# battiny_power_breakout.net
KiCad netlist of a schematic drawn in EAGLE
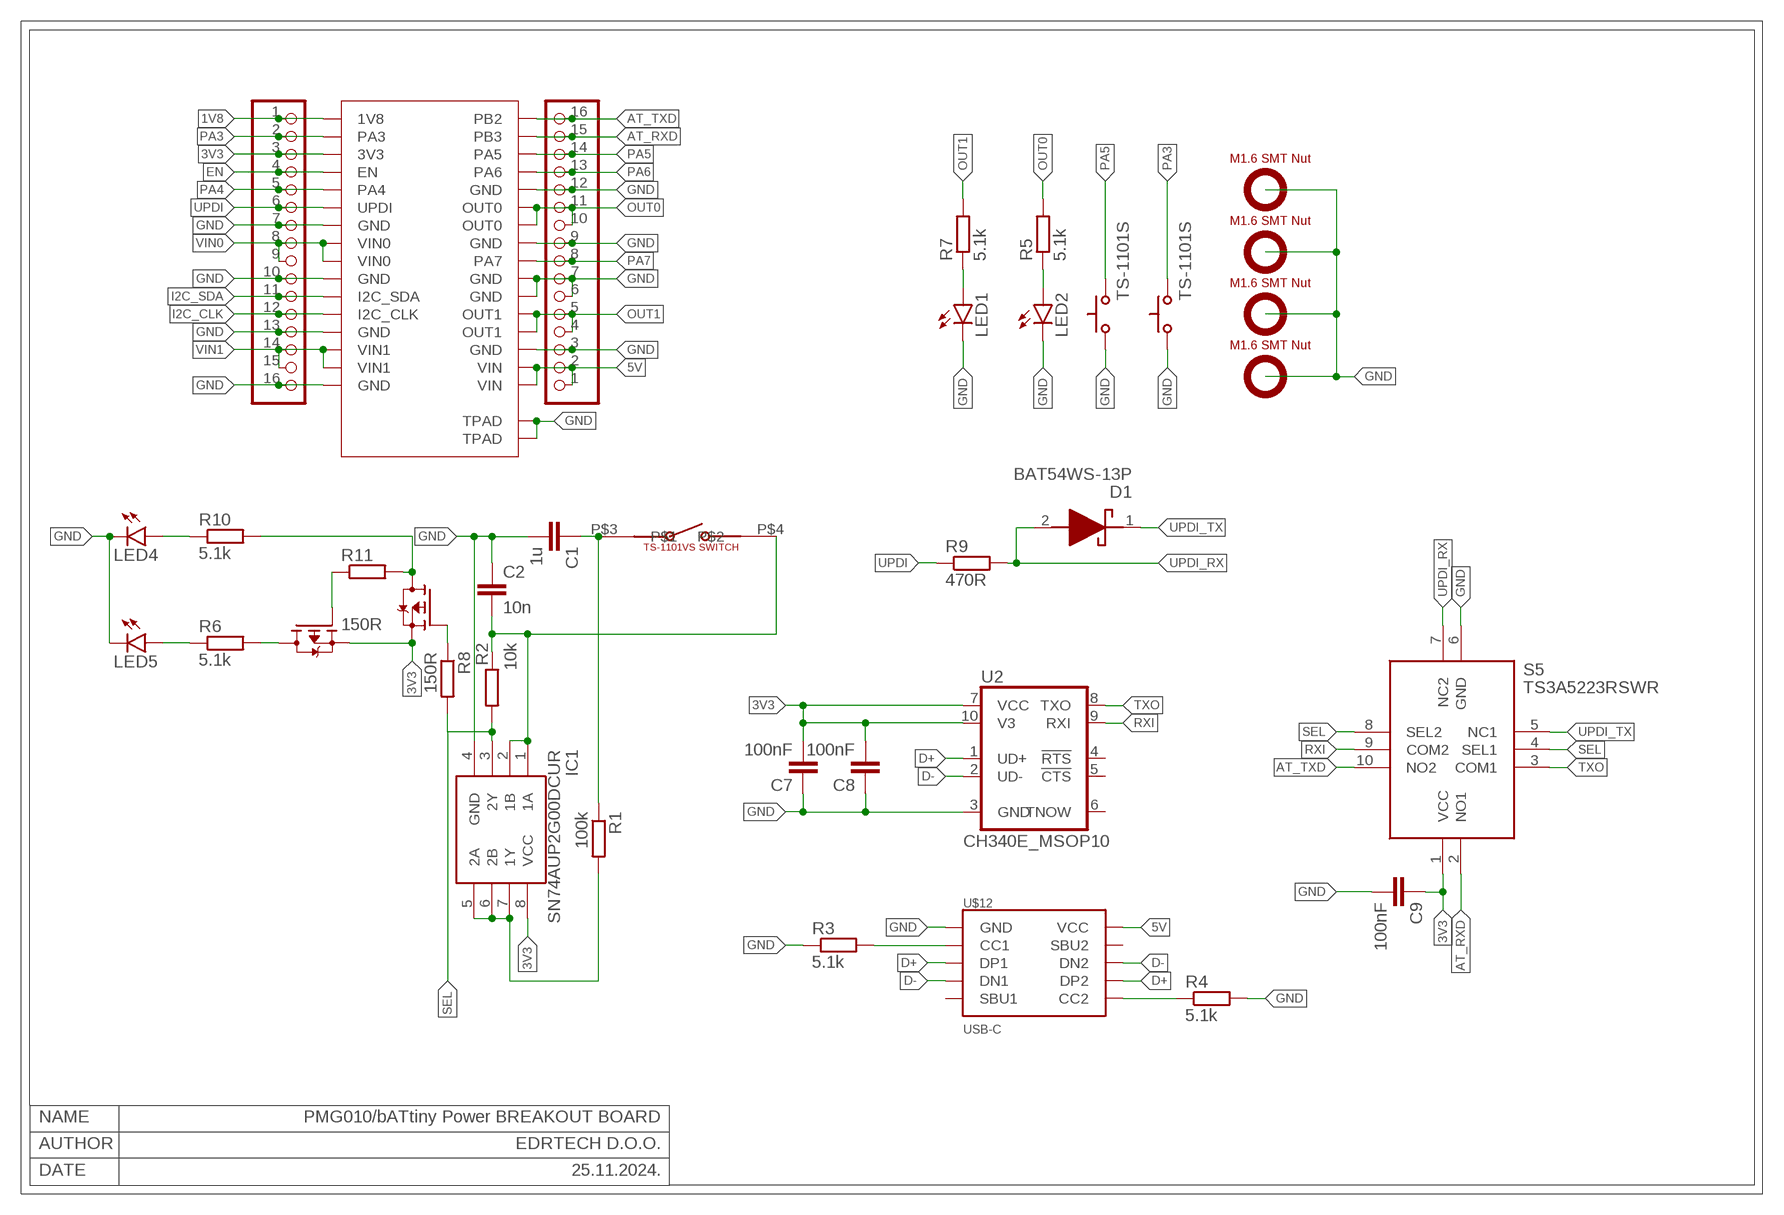
[diagram p0: schematic, sheet 1]

(export (version "E")
  (design (tool "Eeschema 10.0.6"))
  (components
    (comp (ref "C1")
      (value "1u")
      (footprint "eagle-import:C0402")
      (libsource (lib "eagle-import") (part "C-EUC0402"))
    )
    (comp (ref "C2")
      (value "10n")
      (footprint "eagle-import:C0402")
      (libsource (lib "eagle-import") (part "C-EUC0402"))
    )
    (comp (ref "C7")
      (value "100nF")
      (footprint "eagle-import:C0402")
      (libsource (lib "eagle-import") (part "C-EUC0402"))
    )
    (comp (ref "C8")
      (value "100nF")
      (footprint "eagle-import:C0402")
      (libsource (lib "eagle-import") (part "C-EUC0402"))
    )
    (comp (ref "C9")
      (value "100nF")
      (footprint "eagle-import:C0402")
      (libsource (lib "eagle-import") (part "C-EUC0402"))
    )
    (comp (ref "D1")
      (value "BAT54WS-13P")
      (footprint "eagle-import:SOD2512X115N")
      (libsource (lib "eagle-import") (part "BAT54WS-13P"))
    )
    (comp (ref "IC1")
      (value "SN74AUP2G00DCUR")
      (footprint "eagle-import:SOP50P310X90-8N")
      (fields (field (name "MOUSER_PART_NUMBER") "595-SN74AUP2G00DCUR"))
      (libsource (lib "eagle-import") (part "SN74AUP2G00DCUR"))
    )
    (comp (ref "JP1")
      (value "PINHD-1X16")
      (footprint "eagle-import:1X16")
      (libsource (lib "eagle-import") (part "PINHD-1X16"))
    )
    (comp (ref "JP2")
      (value "PINHD-1X16")
      (footprint "eagle-import:1X16")
      (libsource (lib "eagle-import") (part "PINHD-1X16"))
    )
    (comp (ref "LED1")
      (value "LEDCHIP-LED0603")
      (footprint "eagle-import:CHIP-LED0603")
      (libsource (lib "eagle-import") (part "LEDCHIP-LED0603"))
    )
    (comp (ref "LED2")
      (value "LEDCHIP-LED0603")
      (footprint "eagle-import:CHIP-LED0603")
      (libsource (lib "eagle-import") (part "LEDCHIP-LED0603"))
    )
    (comp (ref "LED4")
      (value "LEDCHIP-LED0603")
      (footprint "eagle-import:CHIP-LED0603")
      (libsource (lib "eagle-import") (part "LEDCHIP-LED0603"))
    )
    (comp (ref "LED5")
      (value "LEDCHIP-LED0603")
      (footprint "eagle-import:CHIP-LED0603")
      (libsource (lib "eagle-import") (part "LEDCHIP-LED0603"))
    )
    (comp (ref "Q1")
      (value "NTK3139PT1G")
      (footprint "eagle-import:SOTFL40P120X55-3N")
      (fields (field (name "MOUSER_PART_NUMBER") "863-NTK3139PT1G"))
      (libsource (lib "eagle-import") (part "NTK3139PT1G"))
    )
    (comp (ref "Q2")
      (value "NTK3139PT1G")
      (footprint "eagle-import:SOTFL40P120X55-3N")
      (fields (field (name "MOUSER_PART_NUMBER") "863-NTK3139PT1G"))
      (libsource (lib "eagle-import") (part "NTK3139PT1G"))
    )
    (comp (ref "R1")
      (value "100k")
      (footprint "eagle-import:R0402")
      (libsource (lib "eagle-import") (part "R-EU_R0402"))
    )
    (comp (ref "R2")
      (value "10k")
      (footprint "eagle-import:R0402")
      (libsource (lib "eagle-import") (part "R-EU_R0402"))
    )
    (comp (ref "R3")
      (value "5.1k")
      (footprint "eagle-import:R0402")
      (libsource (lib "eagle-import") (part "R-EU_R0402"))
    )
    (comp (ref "R4")
      (value "5.1k")
      (footprint "eagle-import:R0402")
      (libsource (lib "eagle-import") (part "R-EU_R0402"))
    )
    (comp (ref "R5")
      (value "5.1k")
      (footprint "eagle-import:R0402")
      (libsource (lib "eagle-import") (part "R-EU_R0402"))
    )
    (comp (ref "R6")
      (value "5.1k")
      (footprint "eagle-import:R0402")
      (libsource (lib "eagle-import") (part "R-EU_R0402"))
    )
    (comp (ref "R7")
      (value "5.1k")
      (footprint "eagle-import:R0402")
      (libsource (lib "eagle-import") (part "R-EU_R0402"))
    )
    (comp (ref "R8")
      (value "150R")
      (footprint "eagle-import:R0402")
      (libsource (lib "eagle-import") (part "R-EU_R0402"))
    )
    (comp (ref "R9")
      (value "470R")
      (footprint "eagle-import:R0402")
      (libsource (lib "eagle-import") (part "R-EU_R0402"))
    )
    (comp (ref "R10")
      (value "5.1k")
      (footprint "eagle-import:R0402")
      (libsource (lib "eagle-import") (part "R-EU_R0402"))
    )
    (comp (ref "R11")
      (value "150R")
      (footprint "eagle-import:R0402")
      (libsource (lib "eagle-import") (part "R-EU_R0402"))
    )
    (comp (ref "S5")
      (value "TS3A5223RSWR")
      (footprint "eagle-import:RSW(RPUQFNN10)")
      (fields (field (name "MOUSER_PART_NUMBER") "595-TS3A5223RSWR"))
      (libsource (lib "eagle-import") (part "TS3A5223RSWR"))
    )
    (comp (ref "U$1")
      (value "TS-1101S")
      (footprint "eagle-import:TS-1101S")
      (libsource (lib "eagle-import") (part "TS-1101S"))
    )
    (comp (ref "U$2")
      (value "TS-1101VS-C-A-A")
      (footprint "eagle-import:TS-1101VS-C-A-A")
      (libsource (lib "eagle-import") (part "TS-1101VS-C-A-A"))
    )
    (comp (ref "U$3")
      (value "PMG010")
      (footprint "eagle-import:PMG010")
      (libsource (lib "eagle-import") (part "PMG010"))
    )
    (comp (ref "U$4")
      (value "TS-1101S")
      (footprint "eagle-import:TS-1101S")
      (libsource (lib "eagle-import") (part "TS-1101S"))
    )
    (comp (ref "U$8")
      (value "SMTSO16")
      (footprint "eagle-import:SMTSO16")
      (libsource (lib "eagle-import") (part "SMTSO16"))
    )
    (comp (ref "U$9")
      (value "SMTSO16")
      (footprint "eagle-import:SMTSO16")
      (libsource (lib "eagle-import") (part "SMTSO16"))
    )
    (comp (ref "U$10")
      (value "SMTSO16")
      (footprint "eagle-import:SMTSO16")
      (libsource (lib "eagle-import") (part "SMTSO16"))
    )
    (comp (ref "U$11")
      (value "SMTSO16")
      (footprint "eagle-import:SMTSO16")
      (libsource (lib "eagle-import") (part "SMTSO16"))
    )
    (comp (ref "U$12")
      (value "USB-C")
      (footprint "eagle-import:USB-C")
      (libsource (lib "eagle-import") (part "USB-C"))
    )
    (comp (ref "U2")
      (value "CH340E_MSOP10")
      (footprint "eagle-import:MSOP10")
      (fields (field (name "MF") "WCH") (field (name "MP") "CH340E"))
      (libsource (lib "eagle-import") (part "CH340E_MSOP10"))
    )
  )
  (nets
    (net (code "1") (name "1V8") (class "Default")
      (node (ref "JP1") (pin "1") (pinfunction "1_1") (pintype "passive"))
      (node (ref "U$3") (pin "P$1") (pinfunction "1V8_P$1") (pintype "bidirectional"))
    )
    (net (code "2") (name "3V3") (class "Default")
      (node (ref "C7") (pin "2") (pinfunction "2_2") (pintype "passive"))
      (node (ref "C8") (pin "2") (pinfunction "2_2") (pintype "passive"))
      (node (ref "C9") (pin "1") (pinfunction "1_1") (pintype "passive"))
      (node (ref "IC1") (pin "8") (pinfunction "VCC_8") (pintype "bidirectional"))
      (node (ref "JP1") (pin "3") (pinfunction "3_3") (pintype "passive"))
      (node (ref "Q1") (pin "2") (pinfunction "S_2") (pintype "passive"))
      (node (ref "Q2") (pin "2") (pinfunction "S_2") (pintype "passive"))
      (node (ref "S5") (pin "1") (pinfunction "VCC_1") (pintype "power_in"))
      (node (ref "U$3") (pin "P$3") (pinfunction "3V3_P$3") (pintype "bidirectional"))
      (node (ref "U2") (pin "10") (pinfunction "V3_10") (pintype "bidirectional"))
      (node (ref "U2") (pin "7") (pinfunction "VCC_7") (pintype "bidirectional"))
    )
    (net (code "3") (name "5V") (class "Default")
      (node (ref "JP2") (pin "1") (pinfunction "1_1") (pintype "passive"))
      (node (ref "JP2") (pin "2") (pinfunction "2_2") (pintype "passive"))
      (node (ref "U$12") (pin "VCC@1") (pinfunction "VCC_VCC@1") (pintype "bidirectional"))
      (node (ref "U$12") (pin "VCC@2") (pinfunction "VCC_VCC@2") (pintype "bidirectional"))
      (node (ref "U$3") (pin "P$17") (pinfunction "VIN_P$17") (pintype "bidirectional"))
      (node (ref "U$3") (pin "P$18") (pinfunction "VIN_P$18") (pintype "bidirectional"))
    )
    (net (code "4") (name "AT_RXD") (class "Default")
      (node (ref "JP2") (pin "15") (pinfunction "15_15") (pintype "passive"))
      (node (ref "S5") (pin "2") (pinfunction "NO1_2") (pintype "bidirectional"))
      (node (ref "U$3") (pin "P$31") (pinfunction "PB3_P$31") (pintype "bidirectional"))
    )
    (net (code "5") (name "AT_TXD") (class "Default")
      (node (ref "JP2") (pin "16") (pinfunction "16_16") (pintype "passive"))
      (node (ref "S5") (pin "10") (pinfunction "NO2_10") (pintype "bidirectional"))
      (node (ref "U$3") (pin "P$32") (pinfunction "PB2_P$32") (pintype "bidirectional"))
    )
    (net (code "6") (name "D+") (class "Default")
      (node (ref "U$12") (pin "DP1") (pinfunction "DP1_DP1") (pintype "bidirectional"))
      (node (ref "U$12") (pin "DP2") (pinfunction "DP2_DP2") (pintype "bidirectional"))
      (node (ref "U2") (pin "1") (pinfunction "UD+_1") (pintype "bidirectional"))
    )
    (net (code "7") (name "D-") (class "Default")
      (node (ref "U$12") (pin "DN1") (pinfunction "DN1_DN1") (pintype "bidirectional"))
      (node (ref "U$12") (pin "DN2") (pinfunction "DN2_DN2") (pintype "bidirectional"))
      (node (ref "U2") (pin "2") (pinfunction "UD-_2") (pintype "bidirectional"))
    )
    (net (code "8") (name "EN") (class "Default")
      (node (ref "JP1") (pin "4") (pinfunction "4_4") (pintype "passive"))
      (node (ref "U$3") (pin "P$4") (pinfunction "EN_P$4") (pintype "bidirectional"))
    )
    (net (code "9") (name "GND") (class "Default")
      (node (ref "C1") (pin "2") (pinfunction "2_2") (pintype "passive"))
      (node (ref "C2") (pin "1") (pinfunction "1_1") (pintype "passive"))
      (node (ref "C7") (pin "1") (pinfunction "1_1") (pintype "passive"))
      (node (ref "C8") (pin "1") (pinfunction "1_1") (pintype "passive"))
      (node (ref "C9") (pin "2") (pinfunction "2_2") (pintype "passive"))
      (node (ref "IC1") (pin "4") (pinfunction "GND_4") (pintype "bidirectional"))
      (node (ref "JP1") (pin "10") (pinfunction "10_10") (pintype "passive"))
      (node (ref "JP1") (pin "13") (pinfunction "13_13") (pintype "passive"))
      (node (ref "JP1") (pin "16") (pinfunction "16_16") (pintype "passive"))
      (node (ref "JP1") (pin "7") (pinfunction "7_7") (pintype "passive"))
      (node (ref "JP2") (pin "12") (pinfunction "12_12") (pintype "passive"))
      (node (ref "JP2") (pin "3") (pinfunction "3_3") (pintype "passive"))
      (node (ref "JP2") (pin "6") (pinfunction "6_6") (pintype "passive"))
      (node (ref "JP2") (pin "7") (pinfunction "7_7") (pintype "passive"))
      (node (ref "JP2") (pin "9") (pinfunction "9_9") (pintype "passive"))
      (node (ref "LED1") (pin "C") (pinfunction "C_C") (pintype "passive"))
      (node (ref "LED2") (pin "C") (pinfunction "C_C") (pintype "passive"))
      (node (ref "LED4") (pin "C") (pinfunction "C_C") (pintype "passive"))
      (node (ref "LED5") (pin "C") (pinfunction "C_C") (pintype "passive"))
      (node (ref "R3") (pin "1") (pinfunction "1_1") (pintype "passive"))
      (node (ref "R4") (pin "2") (pinfunction "2_2") (pintype "passive"))
      (node (ref "S5") (pin "6") (pinfunction "GND_6") (pintype "power_in"))
      (node (ref "U$1") (pin "P$1") (pinfunction "1_P$1") (pintype "bidirectional"))
      (node (ref "U$10") (pin "P$1") (pinfunction "P$1_P$1") (pintype "bidirectional"))
      (node (ref "U$11") (pin "P$1") (pinfunction "P$1_P$1") (pintype "bidirectional"))
      (node (ref "U$12") (pin "GND@1") (pinfunction "GND_GND@1") (pintype "bidirectional"))
      (node (ref "U$12") (pin "GND@2") (pinfunction "GND_GND@2") (pintype "bidirectional"))
      (node (ref "U$12") (pin "P$1") (pinfunction "GND_P$1") (pintype "bidirectional"))
      (node (ref "U$12") (pin "P$2") (pinfunction "GND_P$2") (pintype "bidirectional"))
      (node (ref "U$12") (pin "P$3") (pinfunction "GND_P$3") (pintype "bidirectional"))
      (node (ref "U$12") (pin "P$4") (pinfunction "GND_P$4") (pintype "bidirectional"))
      (node (ref "U$3") (pin "P$10") (pinfunction "GND_P$10") (pintype "bidirectional"))
      (node (ref "U$3") (pin "P$13") (pinfunction "GND_P$13") (pintype "bidirectional"))
      (node (ref "U$3") (pin "P$16") (pinfunction "GND_P$16") (pintype "bidirectional"))
      (node (ref "U$3") (pin "P$19") (pinfunction "GND_P$19") (pintype "bidirectional"))
      (node (ref "U$3") (pin "P$22") (pinfunction "GND_P$22") (pintype "bidirectional"))
      (node (ref "U$3") (pin "P$23") (pinfunction "GND_P$23") (pintype "bidirectional"))
      (node (ref "U$3") (pin "P$25") (pinfunction "GND_P$25") (pintype "bidirectional"))
      (node (ref "U$3") (pin "P$28") (pinfunction "GND_P$28") (pintype "bidirectional"))
      (node (ref "U$3") (pin "P$33") (pinfunction "TPAD_P$33") (pintype "bidirectional"))
      (node (ref "U$3") (pin "P$34") (pinfunction "TPAD_P$34") (pintype "bidirectional"))
      (node (ref "U$3") (pin "P$7") (pinfunction "GND_P$7") (pintype "bidirectional"))
      (node (ref "U$4") (pin "P$1") (pinfunction "1_P$1") (pintype "bidirectional"))
      (node (ref "U$8") (pin "P$1") (pinfunction "P$1_P$1") (pintype "bidirectional"))
      (node (ref "U$9") (pin "P$1") (pinfunction "P$1_P$1") (pintype "bidirectional"))
      (node (ref "U2") (pin "3") (pinfunction "GND_3") (pintype "bidirectional"))
    )
    (net (code "10") (name "I2C_CLK") (class "Default")
      (node (ref "JP1") (pin "12") (pinfunction "12_12") (pintype "passive"))
      (node (ref "U$3") (pin "P$12") (pinfunction "I2C_CLK_P$12") (pintype "bidirectional"))
    )
    (net (code "11") (name "I2C_SDA") (class "Default")
      (node (ref "JP1") (pin "11") (pinfunction "11_11") (pintype "passive"))
      (node (ref "U$3") (pin "P$11") (pinfunction "I2C_SDA_P$11") (pintype "bidirectional"))
    )
    (net (code "12") (name "Net-(IC1-1A)") (class "Default")
      (node (ref "C2") (pin "2") (pinfunction "2_2") (pintype "passive"))
      (node (ref "IC1") (pin "1") (pinfunction "1A_1") (pintype "bidirectional"))
      (node (ref "IC1") (pin "2") (pinfunction "1B_2") (pintype "bidirectional"))
      (node (ref "R2") (pin "1") (pinfunction "1_1") (pintype "passive"))
      (node (ref "U$2") (pin "P$4") (pinfunction "P$2_P$4") (pintype "bidirectional"))
    )
    (net (code "13") (name "Net-(IC1-1Y)") (class "Default")
      (node (ref "IC1") (pin "5") (pinfunction "2A_5") (pintype "bidirectional"))
      (node (ref "IC1") (pin "6") (pinfunction "2B_6") (pintype "bidirectional"))
      (node (ref "IC1") (pin "7") (pinfunction "1Y_7") (pintype "bidirectional"))
      (node (ref "R1") (pin "2") (pinfunction "2_2") (pintype "passive"))
    )
    (net (code "14") (name "Net-(LED1-PadA)") (class "Default")
      (node (ref "LED1") (pin "A") (pinfunction "A_A") (pintype "passive"))
      (node (ref "R7") (pin "1") (pinfunction "1_1") (pintype "passive"))
    )
    (net (code "15") (name "Net-(LED2-PadA)") (class "Default")
      (node (ref "LED2") (pin "A") (pinfunction "A_A") (pintype "passive"))
      (node (ref "R5") (pin "1") (pinfunction "1_1") (pintype "passive"))
    )
    (net (code "16") (name "Net-(LED4-PadA)") (class "Default")
      (node (ref "LED4") (pin "A") (pinfunction "A_A") (pintype "passive"))
      (node (ref "R10") (pin "1") (pinfunction "1_1") (pintype "passive"))
    )
    (net (code "17") (name "Net-(LED5-PadA)") (class "Default")
      (node (ref "LED5") (pin "A") (pinfunction "A_A") (pintype "passive"))
      (node (ref "R6") (pin "1") (pinfunction "1_1") (pintype "passive"))
    )
    (net (code "18") (name "Net-(Q1-D)") (class "Default")
      (node (ref "Q1") (pin "3") (pinfunction "D_3") (pintype "passive"))
      (node (ref "R10") (pin "2") (pinfunction "2_2") (pintype "passive"))
      (node (ref "R11") (pin "2") (pinfunction "2_2") (pintype "passive"))
    )
    (net (code "19") (name "Net-(Q1-G)") (class "Default")
      (node (ref "Q1") (pin "1") (pinfunction "G_1") (pintype "passive"))
      (node (ref "R8") (pin "1") (pinfunction "1_1") (pintype "passive"))
    )
    (net (code "20") (name "Net-(Q2-D)") (class "Default")
      (node (ref "Q2") (pin "3") (pinfunction "D_3") (pintype "passive"))
      (node (ref "R6") (pin "2") (pinfunction "2_2") (pintype "passive"))
    )
    (net (code "21") (name "Net-(Q2-G)") (class "Default")
      (node (ref "Q2") (pin "1") (pinfunction "G_1") (pintype "passive"))
      (node (ref "R11") (pin "1") (pinfunction "1_1") (pintype "passive"))
    )
    (net (code "22") (name "Net-(R3-Pad2)") (class "Default")
      (node (ref "R3") (pin "2") (pinfunction "2_2") (pintype "passive"))
      (node (ref "U$12") (pin "CC1") (pinfunction "CC1_CC1") (pintype "bidirectional"))
    )
    (net (code "23") (name "Net-(R4-Pad1)") (class "Default")
      (node (ref "R4") (pin "1") (pinfunction "1_1") (pintype "passive"))
      (node (ref "U$12") (pin "CC2") (pinfunction "CC2_CC2") (pintype "bidirectional"))
    )
    (net (code "24") (name "Net-(U$2-P$1)") (class "Default")
      (node (ref "C1") (pin "1") (pinfunction "1_1") (pintype "passive"))
      (node (ref "R1") (pin "1") (pinfunction "1_1") (pintype "passive"))
      (node (ref "U$2") (pin "P$3") (pinfunction "P$1_P$3") (pintype "bidirectional"))
    )
    (net (code "25") (name "OUT0") (class "Default")
      (node (ref "JP2") (pin "10") (pinfunction "10_10") (pintype "passive"))
      (node (ref "JP2") (pin "11") (pinfunction "11_11") (pintype "passive"))
      (node (ref "R5") (pin "2") (pinfunction "2_2") (pintype "passive"))
      (node (ref "U$3") (pin "P$26") (pinfunction "OUT0_P$26") (pintype "bidirectional"))
      (node (ref "U$3") (pin "P$27") (pinfunction "OUT0_P$27") (pintype "bidirectional"))
    )
    (net (code "26") (name "OUT1") (class "Default")
      (node (ref "JP2") (pin "4") (pinfunction "4_4") (pintype "passive"))
      (node (ref "JP2") (pin "5") (pinfunction "5_5") (pintype "passive"))
      (node (ref "R7") (pin "2") (pinfunction "2_2") (pintype "passive"))
      (node (ref "U$3") (pin "P$20") (pinfunction "OUT1_P$20") (pintype "bidirectional"))
      (node (ref "U$3") (pin "P$21") (pinfunction "OUT1_P$21") (pintype "bidirectional"))
    )
    (net (code "27") (name "PA3") (class "Default")
      (node (ref "JP1") (pin "2") (pinfunction "2_2") (pintype "passive"))
      (node (ref "U$3") (pin "P$2") (pinfunction "PA3_P$2") (pintype "bidirectional"))
      (node (ref "U$4") (pin "P$2") (pinfunction "2_P$2") (pintype "bidirectional"))
    )
    (net (code "28") (name "PA4") (class "Default")
      (node (ref "JP1") (pin "5") (pinfunction "5_5") (pintype "passive"))
      (node (ref "U$3") (pin "P$5") (pinfunction "PA4_P$5") (pintype "bidirectional"))
    )
    (net (code "29") (name "PA5") (class "Default")
      (node (ref "JP2") (pin "14") (pinfunction "14_14") (pintype "passive"))
      (node (ref "U$1") (pin "P$2") (pinfunction "2_P$2") (pintype "bidirectional"))
      (node (ref "U$3") (pin "P$30") (pinfunction "PA5_P$30") (pintype "bidirectional"))
    )
    (net (code "30") (name "PA6") (class "Default")
      (node (ref "JP2") (pin "13") (pinfunction "13_13") (pintype "passive"))
      (node (ref "U$3") (pin "P$29") (pinfunction "PA6_P$29") (pintype "bidirectional"))
    )
    (net (code "31") (name "PA7") (class "Default")
      (node (ref "JP2") (pin "8") (pinfunction "8_8") (pintype "passive"))
      (node (ref "U$3") (pin "P$24") (pinfunction "PA7_P$24") (pintype "bidirectional"))
    )
    (net (code "32") (name "RXI") (class "Default")
      (node (ref "S5") (pin "9") (pinfunction "COM2_9") (pintype "bidirectional"))
      (node (ref "U2") (pin "9") (pinfunction "RXI_9") (pintype "bidirectional"))
    )
    (net (code "33") (name "SEL") (class "Default")
      (node (ref "IC1") (pin "3") (pinfunction "2Y_3") (pintype "bidirectional"))
      (node (ref "R2") (pin "2") (pinfunction "2_2") (pintype "passive"))
      (node (ref "R8") (pin "2") (pinfunction "2_2") (pintype "passive"))
      (node (ref "S5") (pin "4") (pinfunction "SEL1_4") (pintype "bidirectional"))
      (node (ref "S5") (pin "8") (pinfunction "SEL2_8") (pintype "bidirectional"))
    )
    (net (code "34") (name "TXO") (class "Default")
      (node (ref "S5") (pin "3") (pinfunction "COM1_3") (pintype "bidirectional"))
      (node (ref "U2") (pin "8") (pinfunction "TXO_8") (pintype "bidirectional"))
    )
    (net (code "35") (name "UPDI") (class "Default")
      (node (ref "JP1") (pin "6") (pinfunction "6_6") (pintype "passive"))
      (node (ref "R9") (pin "1") (pinfunction "1_1") (pintype "passive"))
      (node (ref "U$3") (pin "P$6") (pinfunction "UPDI_P$6") (pintype "bidirectional"))
    )
    (net (code "36") (name "UPDI_RX") (class "Default")
      (node (ref "D1") (pin "2") (pinfunction "A_2") (pintype "bidirectional"))
      (node (ref "R9") (pin "2") (pinfunction "2_2") (pintype "passive"))
      (node (ref "S5") (pin "7") (pinfunction "NC2_7") (pintype "bidirectional"))
    )
    (net (code "37") (name "UPDI_TX") (class "Default")
      (node (ref "D1") (pin "1") (pinfunction "K_1") (pintype "bidirectional"))
      (node (ref "S5") (pin "5") (pinfunction "NC1_5") (pintype "bidirectional"))
    )
    (net (code "38") (name "VIN0") (class "Default")
      (node (ref "JP1") (pin "8") (pinfunction "8_8") (pintype "passive"))
      (node (ref "JP1") (pin "9") (pinfunction "9_9") (pintype "passive"))
      (node (ref "U$3") (pin "P$8") (pinfunction "VIN0_P$8") (pintype "bidirectional"))
      (node (ref "U$3") (pin "P$9") (pinfunction "VIN0_P$9") (pintype "bidirectional"))
    )
    (net (code "39") (name "VIN1") (class "Default")
      (node (ref "JP1") (pin "14") (pinfunction "14_14") (pintype "passive"))
      (node (ref "JP1") (pin "15") (pinfunction "15_15") (pintype "passive"))
      (node (ref "U$3") (pin "P$14") (pinfunction "VIN1_P$14") (pintype "bidirectional"))
      (node (ref "U$3") (pin "P$15") (pinfunction "VIN1_P$15") (pintype "bidirectional"))
    )
    (net (code "40") (name "unconnected-(U$12-PadSBU1)") (class "Default")
      (node (ref "U$12") (pin "SBU1") (pinfunction "SBU1_SBU1") (pintype "bidirectional"))
    )
    (net (code "41") (name "unconnected-(U$12-PadSBU2)") (class "Default")
      (node (ref "U$12") (pin "SBU2") (pinfunction "SBU2_SBU2") (pintype "bidirectional"))
    )
    (net (code "42") (name "unconnected-(U2-TNOW-Pad6)") (class "Default")
      (node (ref "U2") (pin "6") (pinfunction "TNOW_6") (pintype "bidirectional"))
    )
    (net (code "43") (name "unconnected-(U2-~{CTS}-Pad5)") (class "Default")
      (node (ref "U2") (pin "5") (pinfunction "~{CTS}_5") (pintype "bidirectional"))
    )
    (net (code "44") (name "unconnected-(U2-~{RTS}-Pad4)") (class "Default")
      (node (ref "U2") (pin "4") (pinfunction "~{RTS}_4") (pintype "bidirectional"))
    )
  )
)
